# Adafruit_FT232H_Original.net
KiCad netlist of a schematic drawn in EAGLE
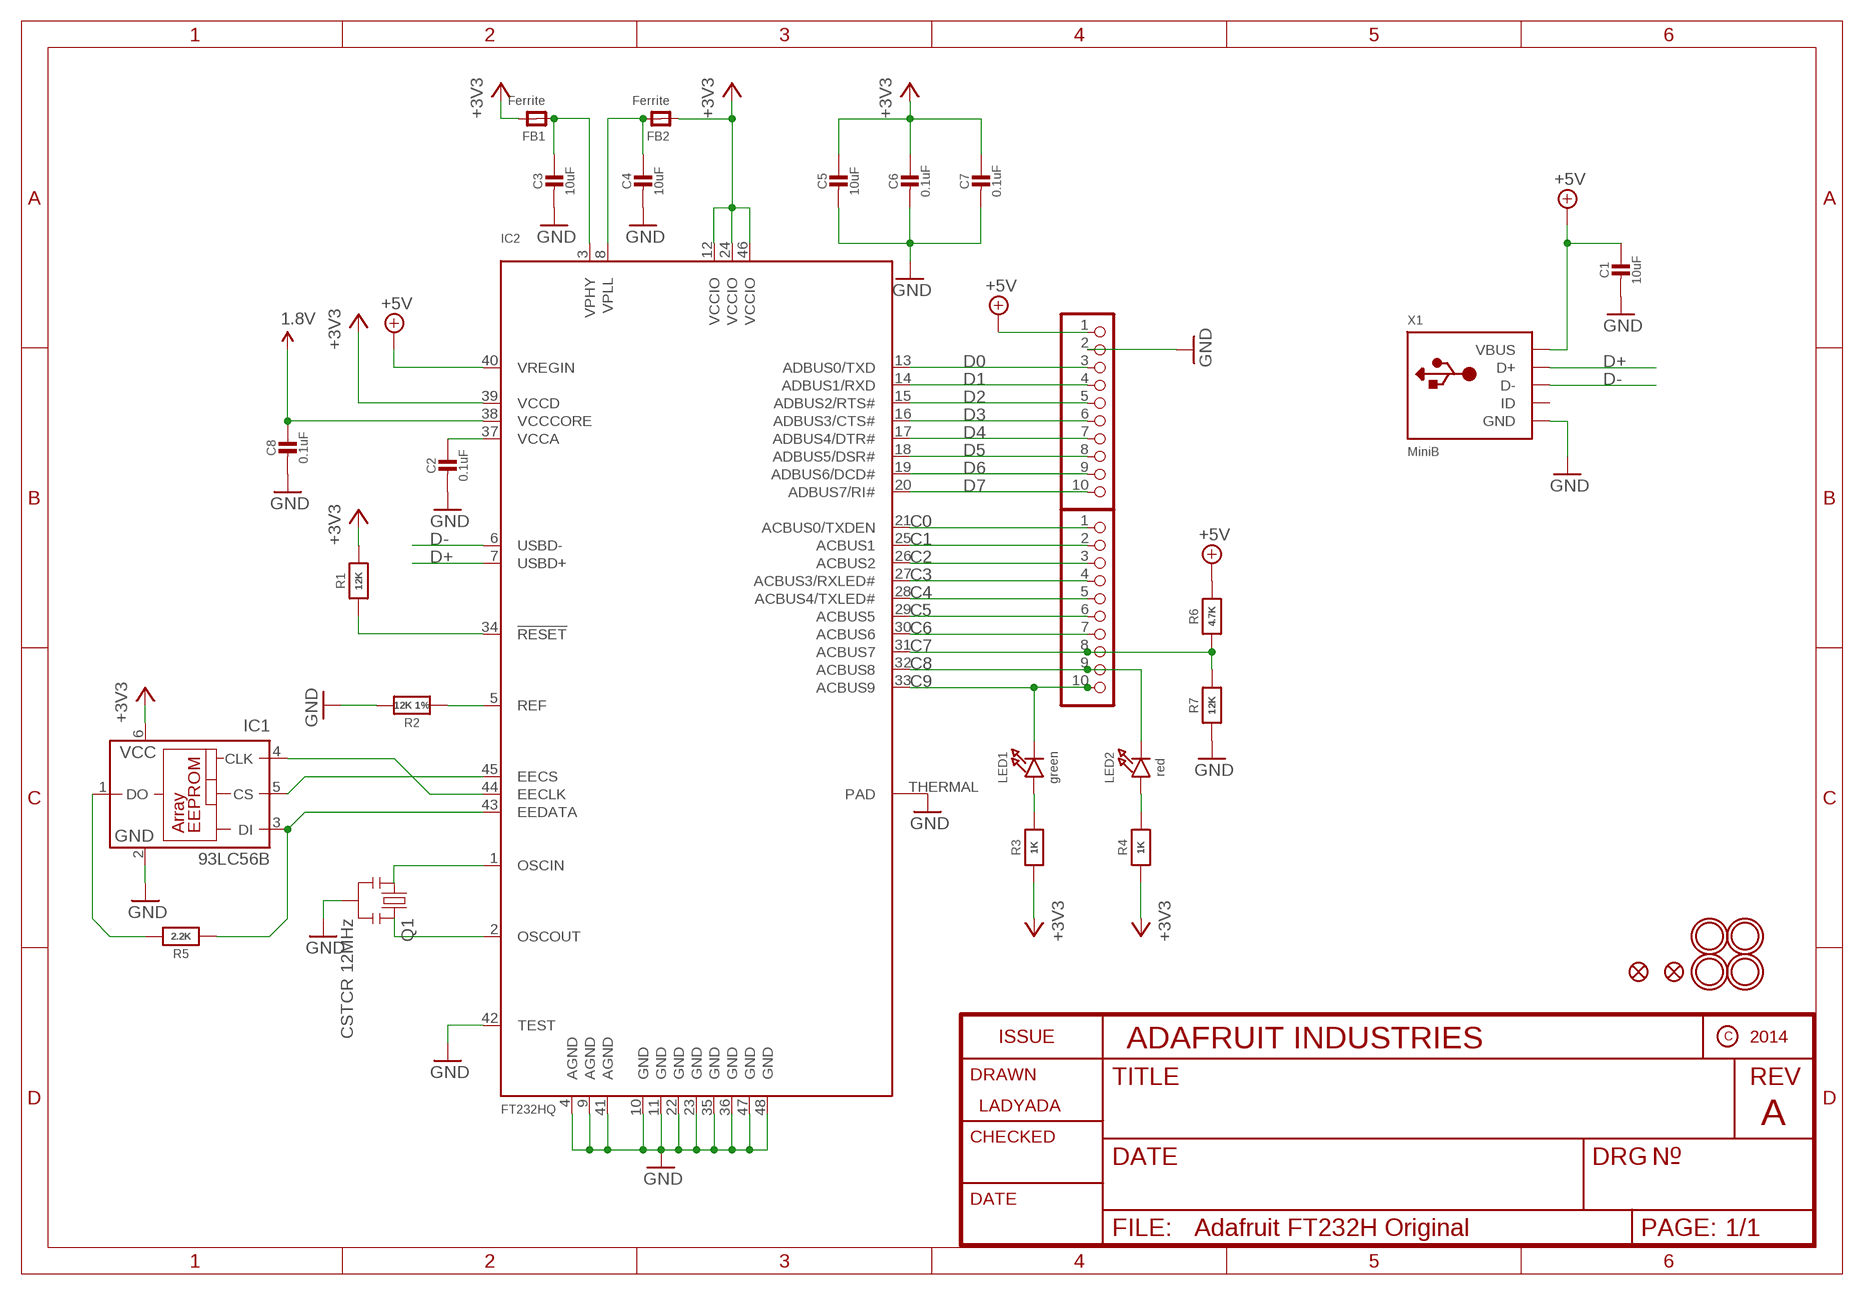
[diagram p0: schematic, sheet 1]

(export (version "E")
  (design (tool "Eeschema 10.0.6"))
  (components
    (comp (ref "C1")
      (value "10uF")
      (footprint "eagle-import:0805-NO")
      (libsource (lib "eagle-import") (part "CAP_CERAMIC0805-NOOUTLINE"))
    )
    (comp (ref "C2")
      (value "0.1uF")
      (footprint "eagle-import:0805-NO")
      (libsource (lib "eagle-import") (part "CAP_CERAMIC0805-NOOUTLINE"))
    )
    (comp (ref "C3")
      (value "10uF")
      (footprint "eagle-import:0805-NO")
      (libsource (lib "eagle-import") (part "CAP_CERAMIC0805-NOOUTLINE"))
    )
    (comp (ref "C4")
      (value "10uF")
      (footprint "eagle-import:0805-NO")
      (libsource (lib "eagle-import") (part "CAP_CERAMIC0805-NOOUTLINE"))
    )
    (comp (ref "C5")
      (value "10uF")
      (footprint "eagle-import:0805-NO")
      (libsource (lib "eagle-import") (part "CAP_CERAMIC0805-NOOUTLINE"))
    )
    (comp (ref "C6")
      (value "0.1uF")
      (footprint "eagle-import:0805-NO")
      (libsource (lib "eagle-import") (part "CAP_CERAMIC0805-NOOUTLINE"))
    )
    (comp (ref "C7")
      (value "0.1uF")
      (footprint "eagle-import:0805-NO")
      (libsource (lib "eagle-import") (part "CAP_CERAMIC0805-NOOUTLINE"))
    )
    (comp (ref "C8")
      (value "0.1uF")
      (footprint "eagle-import:0805-NO")
      (libsource (lib "eagle-import") (part "CAP_CERAMIC0805-NOOUTLINE"))
    )
    (comp (ref "FB1")
      (value "Ferrite")
      (footprint "eagle-import:_0805")
      (libsource (lib "eagle-import") (part "FERRITE_0805"))
    )
    (comp (ref "FB2")
      (value "Ferrite")
      (footprint "eagle-import:_0805")
      (libsource (lib "eagle-import") (part "FERRITE_0805"))
    )
    (comp (ref "FID1")
      (value "FIDUCIAL\"\"")
      (footprint "eagle-import:FIDUCIAL_1MM")
      (libsource (lib "eagle-import") (part "FIDUCIAL{dblquote}{dblquote}"))
    )
    (comp (ref "FID2")
      (value "FIDUCIAL\"\"")
      (footprint "eagle-import:FIDUCIAL_1MM")
      (libsource (lib "eagle-import") (part "FIDUCIAL{dblquote}{dblquote}"))
    )
    (comp (ref "IC1")
      (value "93LC56B")
      (footprint "eagle-import:SOT23-6")
      (fields (field (name "MF") "MICROCHIP") (field (name "MPN") "93LC76AT-I/OT"))
      (libsource (lib "eagle-import") (part "9376?ALC"))
    )
    (comp (ref "IC2")
      (value "FT232HQ")
      (footprint "eagle-import:QFN48_8MM")
      (libsource (lib "eagle-import") (part "FT232HQ"))
    )
    (comp (ref "LED1")
      (value "green")
      (footprint "eagle-import:CHIPLED_0805_NOOUTLINE")
      (libsource (lib "eagle-import") (part "LED0805_NOOUTLINE"))
    )
    (comp (ref "LED2")
      (value "red")
      (footprint "eagle-import:CHIPLED_0805_NOOUTLINE")
      (libsource (lib "eagle-import") (part "LED0805_NOOUTLINE"))
    )
    (comp (ref "Q1")
      (value "CSTCR 12MHz")
      (footprint "eagle-import:RESONATOR-SMD")
      (libsource (lib "eagle-import") (part "RESONATORSMD"))
    )
    (comp (ref "R1")
      (value "12K")
      (footprint "eagle-import:0805-NO")
      (libsource (lib "eagle-import") (part "RESISTOR0805_NOOUTLINE"))
    )
    (comp (ref "R2")
      (value "12K 1%")
      (footprint "eagle-import:0805-NO")
      (libsource (lib "eagle-import") (part "RESISTOR0805_NOOUTLINE"))
    )
    (comp (ref "R3")
      (value "1K")
      (footprint "eagle-import:0805-NO")
      (libsource (lib "eagle-import") (part "RESISTOR0805_NOOUTLINE"))
    )
    (comp (ref "R4")
      (value "1K")
      (footprint "eagle-import:0805-NO")
      (libsource (lib "eagle-import") (part "RESISTOR0805_NOOUTLINE"))
    )
    (comp (ref "R5")
      (value "2.2K")
      (footprint "eagle-import:_0805MP")
      (libsource (lib "eagle-import") (part "RESISTOR_0805MP"))
    )
    (comp (ref "R6")
      (value "4.7K")
      (footprint "eagle-import:0805-NO")
      (libsource (lib "eagle-import") (part "RESISTOR0805_NOOUTLINE"))
    )
    (comp (ref "R7")
      (value "12K")
      (footprint "eagle-import:0805-NO")
      (libsource (lib "eagle-import") (part "RESISTOR0805_NOOUTLINE"))
    )
    (comp (ref "U$2")
      (value "PINHD-1X10")
      (footprint "eagle-import:1X10-BIG")
      (libsource (lib "eagle-import") (part "PINHD-1X10"))
    )
    (comp (ref "U$3")
      (value "PINHD-1X10")
      (footprint "eagle-import:1X10-BIG")
      (libsource (lib "eagle-import") (part "PINHD-1X10"))
    )
    (comp (ref "U$4")
      (value "MOUNTINGHOLE2.5")
      (footprint "eagle-import:MOUNTINGHOLE_2.5_PLATED")
      (libsource (lib "eagle-import") (part "MOUNTINGHOLE2.5"))
    )
    (comp (ref "U$5")
      (value "MOUNTINGHOLE2.5")
      (footprint "eagle-import:MOUNTINGHOLE_2.5_PLATED")
      (libsource (lib "eagle-import") (part "MOUNTINGHOLE2.5"))
    )
    (comp (ref "U$6")
      (value "MOUNTINGHOLE2.5")
      (footprint "eagle-import:MOUNTINGHOLE_2.5_PLATED")
      (fields (field (name "BOM") "EXCLUDE"))
      (libsource (lib "eagle-import") (part "MOUNTINGHOLE2.5"))
    )
    (comp (ref "U$7")
      (value "MOUNTINGHOLE2.5")
      (footprint "eagle-import:MOUNTINGHOLE_2.5_PLATED")
      (libsource (lib "eagle-import") (part "MOUNTINGHOLE2.5"))
    )
    (comp (ref "X1")
      (value "MiniB")
      (footprint "eagle-import:4UCONN_20329")
      (libsource (lib "eagle-import") (part "USBMICRO_20329"))
    )
  )
  (nets
    (net (code "1") (name "+3V3") (class "Default")
      (node (ref "C5") (pin "1") (pinfunction "1_1") (pintype "passive"))
      (node (ref "C6") (pin "1") (pinfunction "1_1") (pintype "passive"))
      (node (ref "C7") (pin "1") (pinfunction "1_1") (pintype "passive"))
      (node (ref "FB1") (pin "2") (pinfunction "P$2_2") (pintype "passive"))
      (node (ref "FB2") (pin "1") (pinfunction "P$1_1") (pintype "passive"))
      (node (ref "IC1") (pin "6") (pinfunction "VCC_6") (pintype "power_in"))
      (node (ref "IC2") (pin "12") (pinfunction "VCCIO_12") (pintype "power_in"))
      (node (ref "IC2") (pin "24") (pinfunction "VCCIO_24") (pintype "power_in"))
      (node (ref "IC2") (pin "39") (pinfunction "VCCD_39") (pintype "power_in"))
      (node (ref "IC2") (pin "46") (pinfunction "VCCIO_46") (pintype "power_in"))
      (node (ref "R1") (pin "2") (pinfunction "2_2") (pintype "passive"))
      (node (ref "R3") (pin "1") (pinfunction "1_1") (pintype "passive"))
      (node (ref "R4") (pin "1") (pinfunction "1_1") (pintype "passive"))
    )
    (net (code "2") (name "+5V") (class "Default")
      (node (ref "C1") (pin "1") (pinfunction "1_1") (pintype "passive"))
      (node (ref "IC2") (pin "40") (pinfunction "VREGIN_40") (pintype "power_in"))
      (node (ref "R6") (pin "2") (pinfunction "2_2") (pintype "passive"))
      (node (ref "U$2") (pin "1") (pinfunction "1_1") (pintype "passive"))
      (node (ref "X1") (pin "VBUS") (pinfunction "VBUS_VBUS") (pintype "power_in"))
    )
    (net (code "3") (name "/C0") (class "Default")
      (node (ref "IC2") (pin "21") (pinfunction "ACBUS0/TXDEN_21") (pintype "bidirectional"))
      (node (ref "U$3") (pin "1") (pinfunction "1_1") (pintype "passive"))
    )
    (net (code "4") (name "/C1") (class "Default")
      (node (ref "IC2") (pin "25") (pinfunction "ACBUS1_25") (pintype "bidirectional"))
      (node (ref "U$3") (pin "2") (pinfunction "2_2") (pintype "passive"))
    )
    (net (code "5") (name "/C2") (class "Default")
      (node (ref "IC2") (pin "26") (pinfunction "ACBUS2_26") (pintype "bidirectional"))
      (node (ref "U$3") (pin "3") (pinfunction "3_3") (pintype "passive"))
    )
    (net (code "6") (name "/C3") (class "Default")
      (node (ref "IC2") (pin "27") (pinfunction "ACBUS3/RXLED#_27") (pintype "bidirectional"))
      (node (ref "U$3") (pin "4") (pinfunction "4_4") (pintype "passive"))
    )
    (net (code "7") (name "/C4") (class "Default")
      (node (ref "IC2") (pin "28") (pinfunction "ACBUS4/TXLED#_28") (pintype "bidirectional"))
      (node (ref "U$3") (pin "5") (pinfunction "5_5") (pintype "passive"))
    )
    (net (code "8") (name "/C5") (class "Default")
      (node (ref "IC2") (pin "29") (pinfunction "ACBUS5_29") (pintype "bidirectional"))
      (node (ref "U$3") (pin "6") (pinfunction "6_6") (pintype "passive"))
    )
    (net (code "9") (name "/C6") (class "Default")
      (node (ref "IC2") (pin "30") (pinfunction "ACBUS6_30") (pintype "bidirectional"))
      (node (ref "U$3") (pin "7") (pinfunction "7_7") (pintype "passive"))
    )
    (net (code "10") (name "/C7") (class "Default")
      (node (ref "IC2") (pin "31") (pinfunction "ACBUS7_31") (pintype "bidirectional"))
      (node (ref "R6") (pin "1") (pinfunction "1_1") (pintype "passive"))
      (node (ref "R7") (pin "2") (pinfunction "2_2") (pintype "passive"))
      (node (ref "U$3") (pin "8") (pinfunction "8_8") (pintype "passive"))
    )
    (net (code "11") (name "/C8") (class "Default")
      (node (ref "IC2") (pin "32") (pinfunction "ACBUS8_32") (pintype "bidirectional"))
      (node (ref "LED2") (pin "C") (pinfunction "C_C") (pintype "passive"))
      (node (ref "U$3") (pin "9") (pinfunction "9_9") (pintype "passive"))
    )
    (net (code "12") (name "/C9") (class "Default")
      (node (ref "IC2") (pin "33") (pinfunction "ACBUS9_33") (pintype "bidirectional"))
      (node (ref "LED1") (pin "C") (pinfunction "C_C") (pintype "passive"))
      (node (ref "U$3") (pin "10") (pinfunction "10_10") (pintype "passive"))
    )
    (net (code "13") (name "/D+") (class "Default")
      (node (ref "IC2") (pin "7") (pinfunction "USBD+_7") (pintype "bidirectional"))
      (node (ref "X1") (pin "D+") (pinfunction "D+_D+") (pintype "bidirectional"))
    )
    (net (code "14") (name "/D-") (class "Default")
      (node (ref "IC2") (pin "6") (pinfunction "USBD-_6") (pintype "bidirectional"))
      (node (ref "X1") (pin "D-") (pinfunction "D-_D-") (pintype "bidirectional"))
    )
    (net (code "15") (name "/D0") (class "Default")
      (node (ref "IC2") (pin "13") (pinfunction "ADBUS0/TXD_13") (pintype "output"))
      (node (ref "U$2") (pin "3") (pinfunction "3_3") (pintype "passive"))
    )
    (net (code "16") (name "/D1") (class "Default")
      (node (ref "IC2") (pin "14") (pinfunction "ADBUS1/RXD_14") (pintype "input"))
      (node (ref "U$2") (pin "4") (pinfunction "4_4") (pintype "passive"))
    )
    (net (code "17") (name "/D2") (class "Default")
      (node (ref "IC2") (pin "15") (pinfunction "ADBUS2/RTS#_15") (pintype "output"))
      (node (ref "U$2") (pin "5") (pinfunction "5_5") (pintype "passive"))
    )
    (net (code "18") (name "/D3") (class "Default")
      (node (ref "IC2") (pin "16") (pinfunction "ADBUS3/CTS#_16") (pintype "input"))
      (node (ref "U$2") (pin "6") (pinfunction "6_6") (pintype "passive"))
    )
    (net (code "19") (name "/D4") (class "Default")
      (node (ref "IC2") (pin "17") (pinfunction "ADBUS4/DTR#_17") (pintype "output"))
      (node (ref "U$2") (pin "7") (pinfunction "7_7") (pintype "passive"))
    )
    (net (code "20") (name "/D5") (class "Default")
      (node (ref "IC2") (pin "18") (pinfunction "ADBUS5/DSR#_18") (pintype "input"))
      (node (ref "U$2") (pin "8") (pinfunction "8_8") (pintype "passive"))
    )
    (net (code "21") (name "/D6") (class "Default")
      (node (ref "IC2") (pin "19") (pinfunction "ADBUS6/DCD#_19") (pintype "input"))
      (node (ref "U$2") (pin "9") (pinfunction "9_9") (pintype "passive"))
    )
    (net (code "22") (name "/D7") (class "Default")
      (node (ref "IC2") (pin "20") (pinfunction "ADBUS7/RI#_20") (pintype "input"))
      (node (ref "U$2") (pin "10") (pinfunction "10_10") (pintype "passive"))
    )
    (net (code "23") (name "1.8V") (class "Default")
      (node (ref "C8") (pin "1") (pinfunction "1_1") (pintype "passive"))
      (node (ref "IC2") (pin "38") (pinfunction "VCCCORE_38") (pintype "power_in"))
    )
    (net (code "24") (name "GND") (class "Default")
      (node (ref "C1") (pin "2") (pinfunction "2_2") (pintype "passive"))
      (node (ref "C2") (pin "2") (pinfunction "2_2") (pintype "passive"))
      (node (ref "C3") (pin "2") (pinfunction "2_2") (pintype "passive"))
      (node (ref "C4") (pin "2") (pinfunction "2_2") (pintype "passive"))
      (node (ref "C5") (pin "2") (pinfunction "2_2") (pintype "passive"))
      (node (ref "C6") (pin "2") (pinfunction "2_2") (pintype "passive"))
      (node (ref "C7") (pin "2") (pinfunction "2_2") (pintype "passive"))
      (node (ref "C8") (pin "2") (pinfunction "2_2") (pintype "passive"))
      (node (ref "IC1") (pin "2") (pinfunction "GND_2") (pintype "power_in"))
      (node (ref "IC2") (pin "10") (pinfunction "GND_10") (pintype "power_in"))
      (node (ref "IC2") (pin "11") (pinfunction "GND_11") (pintype "power_in"))
      (node (ref "IC2") (pin "22") (pinfunction "GND_22") (pintype "power_in"))
      (node (ref "IC2") (pin "23") (pinfunction "GND_23") (pintype "power_in"))
      (node (ref "IC2") (pin "35") (pinfunction "GND_35") (pintype "power_in"))
      (node (ref "IC2") (pin "36") (pinfunction "GND_36") (pintype "power_in"))
      (node (ref "IC2") (pin "4") (pinfunction "AGND_4") (pintype "power_in"))
      (node (ref "IC2") (pin "41") (pinfunction "AGND_41") (pintype "power_in"))
      (node (ref "IC2") (pin "42") (pinfunction "TEST_42") (pintype "input"))
      (node (ref "IC2") (pin "47") (pinfunction "GND_47") (pintype "power_in"))
      (node (ref "IC2") (pin "48") (pinfunction "GND_48") (pintype "power_in"))
      (node (ref "IC2") (pin "9") (pinfunction "AGND_9") (pintype "power_in"))
      (node (ref "IC2") (pin "THERMAL") (pinfunction "PAD_THERMAL") (pintype "passive"))
      (node (ref "Q1") (pin "2") (pinfunction "2_2") (pintype "passive"))
      (node (ref "R2") (pin "2") (pinfunction "2_2") (pintype "passive"))
      (node (ref "R7") (pin "1") (pinfunction "1_1") (pintype "passive"))
      (node (ref "U$2") (pin "2") (pinfunction "2_2") (pintype "passive"))
      (node (ref "X1") (pin "BASE@1") (pinfunction "GND_BASE@1") (pintype "power_in"))
      (node (ref "X1") (pin "BASE@2") (pinfunction "GND_BASE@2") (pintype "power_in"))
      (node (ref "X1") (pin "GND") (pinfunction "GND_GND") (pintype "power_in"))
      (node (ref "X1") (pin "SPRT@1") (pinfunction "GND_SPRT@1") (pintype "power_in"))
      (node (ref "X1") (pin "SPRT@2") (pinfunction "GND_SPRT@2") (pintype "power_in"))
      (node (ref "X1") (pin "SPRT@3") (pinfunction "GND_SPRT@3") (pintype "power_in"))
      (node (ref "X1") (pin "SPRT@4") (pinfunction "GND_SPRT@4") (pintype "power_in"))
    )
    (net (code "25") (name "Net-(FB1-P$1)") (class "Default")
      (node (ref "C3") (pin "1") (pinfunction "1_1") (pintype "passive"))
      (node (ref "FB1") (pin "1") (pinfunction "P$1_1") (pintype "passive"))
      (node (ref "IC2") (pin "3") (pinfunction "VPHY_3") (pintype "power_in"))
    )
    (net (code "26") (name "Net-(FB2-P$2)") (class "Default")
      (node (ref "C4") (pin "1") (pinfunction "1_1") (pintype "passive"))
      (node (ref "FB2") (pin "2") (pinfunction "P$2_2") (pintype "passive"))
      (node (ref "IC2") (pin "8") (pinfunction "VPLL_8") (pintype "power_in"))
    )
    (net (code "27") (name "Net-(IC1-CLK)") (class "Default")
      (node (ref "IC1") (pin "4") (pinfunction "CLK_4") (pintype "input"))
      (node (ref "IC2") (pin "44") (pinfunction "EECLK_44") (pintype "output"))
    )
    (net (code "28") (name "Net-(IC1-CS)") (class "Default")
      (node (ref "IC1") (pin "5") (pinfunction "CS_5") (pintype "input"))
      (node (ref "IC2") (pin "45") (pinfunction "EECS_45") (pintype "bidirectional"))
    )
    (net (code "29") (name "Net-(IC1-DI)") (class "Default")
      (node (ref "IC1") (pin "3") (pinfunction "DI_3") (pintype "input"))
      (node (ref "IC2") (pin "43") (pinfunction "EEDATA_43") (pintype "bidirectional"))
      (node (ref "R5") (pin "1") (pinfunction "1_1") (pintype "passive"))
    )
    (net (code "30") (name "Net-(IC1-DO)") (class "Default")
      (node (ref "IC1") (pin "1") (pinfunction "DO_1") (pintype "tri_state"))
      (node (ref "R5") (pin "2") (pinfunction "2_2") (pintype "passive"))
    )
    (net (code "31") (name "Net-(IC2-OSCIN)") (class "Default")
      (node (ref "IC2") (pin "1") (pinfunction "OSCIN_1") (pintype "input"))
      (node (ref "Q1") (pin "1") (pinfunction "1_1") (pintype "passive"))
    )
    (net (code "32") (name "Net-(IC2-OSCOUT)") (class "Default")
      (node (ref "IC2") (pin "2") (pinfunction "OSCOUT_2") (pintype "output"))
      (node (ref "Q1") (pin "3") (pinfunction "3_3") (pintype "passive"))
    )
    (net (code "33") (name "Net-(IC2-REF)") (class "Default")
      (node (ref "IC2") (pin "5") (pinfunction "REF_5") (pintype "input"))
      (node (ref "R2") (pin "1") (pinfunction "1_1") (pintype "passive"))
    )
    (net (code "34") (name "Net-(IC2-VCCA)") (class "Default")
      (node (ref "C2") (pin "1") (pinfunction "1_1") (pintype "passive"))
      (node (ref "IC2") (pin "37") (pinfunction "VCCA_37") (pintype "power_in"))
    )
    (net (code "35") (name "Net-(IC2-~{RESET})") (class "Default")
      (node (ref "IC2") (pin "34") (pinfunction "~{RESET}_34") (pintype "input"))
      (node (ref "R1") (pin "1") (pinfunction "1_1") (pintype "passive"))
    )
    (net (code "36") (name "Net-(LED1-PadA)") (class "Default")
      (node (ref "LED1") (pin "A") (pinfunction "A_A") (pintype "passive"))
      (node (ref "R3") (pin "2") (pinfunction "2_2") (pintype "passive"))
    )
    (net (code "37") (name "Net-(LED2-PadA)") (class "Default")
      (node (ref "LED2") (pin "A") (pinfunction "A_A") (pintype "passive"))
      (node (ref "R4") (pin "2") (pinfunction "2_2") (pintype "passive"))
    )
    (net (code "38") (name "unconnected-(X1-PadID)") (class "Default")
      (node (ref "X1") (pin "ID") (pinfunction "ID_ID") (pintype "bidirectional"))
    )
  )
)
